# avroscope.net
KiCad netlist of a schematic drawn in Altium Designer
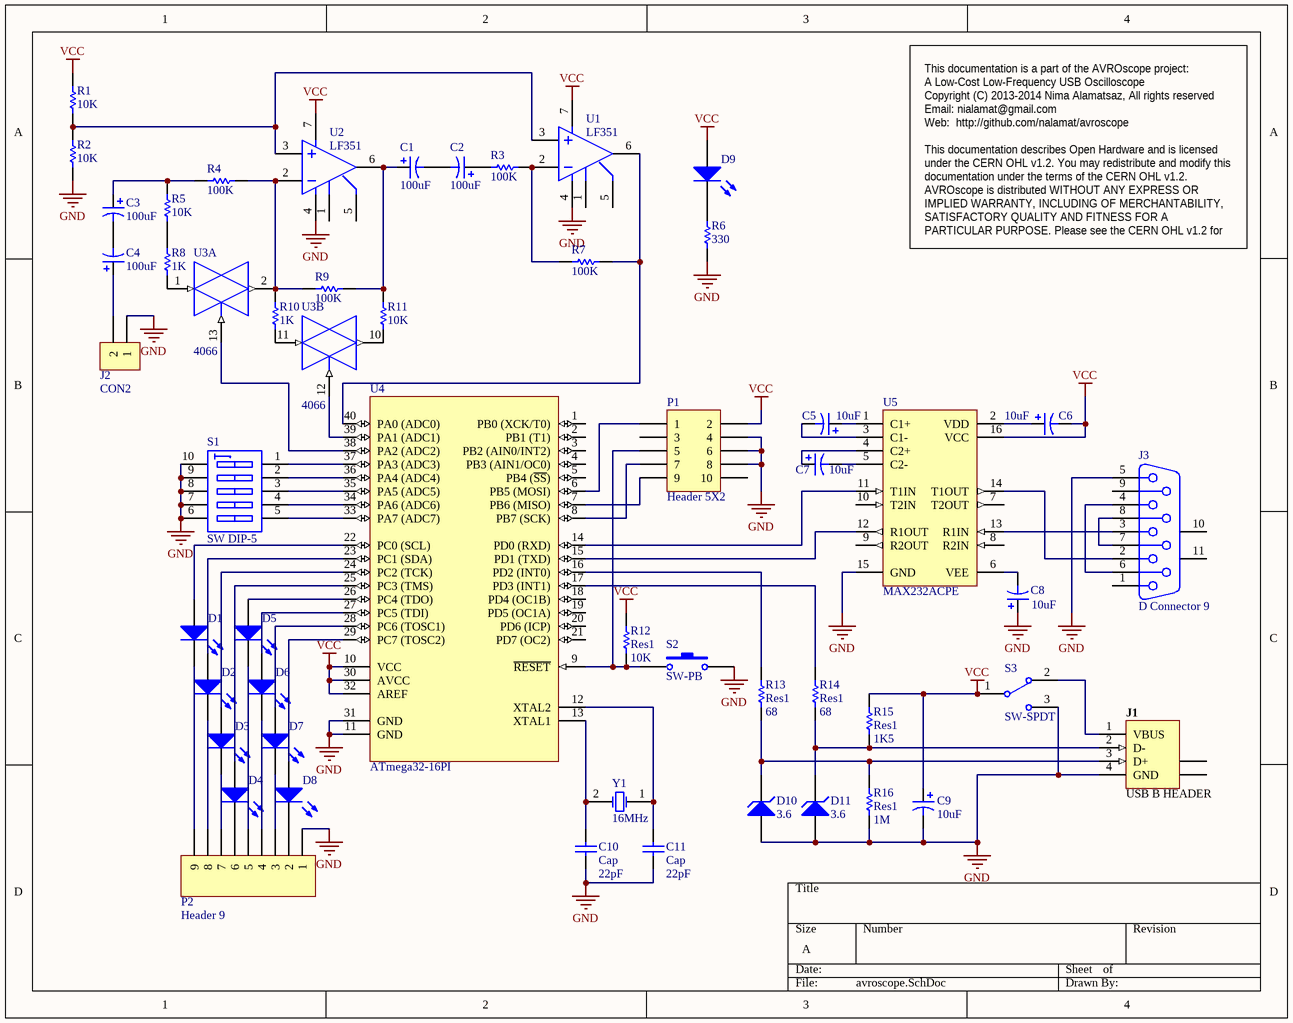
[diagram p0: avroscope.SchDoc]

(export (version "E")
  (design (tool "Eeschema 10.0.6"))
  (components
    (comp (ref "C1")
      (value "100uF")
      (footprint "RB.1/.2")
      (description "Polarized Capacitor (Radial)")
      (fields (field (name "Comment") "Cap Pol1") (field (name "PUBLISHER") "Altium Limited"))
      (libsource (lib "Miscellaneous Devices") (part "Cap Pol1"))
    )
    (comp (ref "C2")
      (value "100uF")
      (footprint "RB.1/.2")
      (description "Polarized Capacitor (Radial)")
      (fields (field (name "Comment") "Cap Pol1") (field (name "PUBLISHER") "Altium Limited"))
      (libsource (lib "Miscellaneous Devices") (part "Cap Pol1"))
    )
    (comp (ref "C3")
      (value "100uF")
      (footprint "RB.1/.2")
      (description "Polarized Capacitor (Radial)")
      (fields (field (name "Comment") "Cap Pol1") (field (name "PUBLISHER") "Altium Limited"))
      (libsource (lib "Miscellaneous Devices") (part "Cap Pol1"))
    )
    (comp (ref "C4")
      (value "100uF")
      (footprint "RB.1/.2")
      (description "Polarized Capacitor (Radial)")
      (fields (field (name "Comment") "Cap Pol1") (field (name "PUBLISHER") "Altium Limited"))
      (libsource (lib "Miscellaneous Devices") (part "Cap Pol1"))
    )
    (comp (ref "C5")
      (value "10uF")
      (footprint "RB.1/.2")
      (description "Polarized Capacitor (Radial)")
      (fields (field (name "Comment") "Cap Pol1") (field (name "PUBLISHER") "Altium Limited"))
      (libsource (lib "Miscellaneous Devices") (part "Cap Pol1"))
    )
    (comp (ref "C6")
      (value "10uF")
      (footprint "RB.1/.2")
      (description "Polarized Capacitor (Radial)")
      (fields (field (name "Comment") "Cap Pol1") (field (name "PUBLISHER") "Altium Limited"))
      (libsource (lib "Miscellaneous Devices") (part "Cap Pol1"))
    )
    (comp (ref "C7")
      (value "10uF")
      (footprint "RB.1/.2")
      (description "Polarized Capacitor (Radial)")
      (fields (field (name "Comment") "Cap Pol1") (field (name "PUBLISHER") "Altium Limited"))
      (libsource (lib "Miscellaneous Devices") (part "Cap Pol1"))
    )
    (comp (ref "C8")
      (value "10uF")
      (footprint "RB.1/.2")
      (description "Polarized Capacitor (Radial)")
      (fields (field (name "Comment") "Cap Pol1") (field (name "PUBLISHER") "Altium Limited"))
      (libsource (lib "Miscellaneous Devices") (part "Cap Pol1"))
    )
    (comp (ref "C9")
      (value "10uF")
      (footprint "RB.1/.2")
      (description "Polarized Capacitor (Radial)")
      (fields (field (name "Comment") "Cap Pol1") (field (name "PUBLISHER") "Altium Limited"))
      (libsource (lib "Miscellaneous Devices") (part "Cap Pol1"))
    )
    (comp (ref "C10")
      (value "Cap")
      (footprint "RAD0.1")
      (description "Capacitor")
      (fields (field (name "ALTIUM_VALUE") "22pF") (field (name "PUBLISHER") "Altium Limited"))
      (libsource (lib "Miscellaneous Devices") (part "Cap"))
    )
    (comp (ref "C11")
      (value "Cap")
      (footprint "RAD0.1")
      (description "Capacitor")
      (fields (field (name "ALTIUM_VALUE") "22pF") (field (name "PUBLISHER") "Altium Limited"))
      (libsource (lib "Miscellaneous Devices") (part "Cap"))
    )
    (comp (ref "D1")
      (value "LED1")
      (footprint "LED .1")
      (description "Typical RED GaAs LED")
      (fields (field (name "PUBLISHER") "Altium Limited"))
      (libsource (lib "Miscellaneous Devices") (part "LED1"))
    )
    (comp (ref "D2")
      (value "LED1")
      (footprint "LED .1")
      (description "Typical RED GaAs LED")
      (fields (field (name "PUBLISHER") "Altium Limited"))
      (libsource (lib "Miscellaneous Devices") (part "LED1"))
    )
    (comp (ref "D3")
      (value "LED1")
      (footprint "LED .1")
      (description "Typical RED GaAs LED")
      (fields (field (name "PUBLISHER") "Altium Limited"))
      (libsource (lib "Miscellaneous Devices") (part "LED1"))
    )
    (comp (ref "D4")
      (value "LED1")
      (footprint "LED .1")
      (description "Typical RED GaAs LED")
      (fields (field (name "PUBLISHER") "Altium Limited"))
      (libsource (lib "Miscellaneous Devices") (part "LED1"))
    )
    (comp (ref "D5")
      (value "LED1")
      (footprint "LED .1")
      (description "Typical RED GaAs LED")
      (fields (field (name "PUBLISHER") "Altium Limited"))
      (libsource (lib "Miscellaneous Devices") (part "LED1"))
    )
    (comp (ref "D6")
      (value "LED1")
      (footprint "LED .1")
      (description "Typical RED GaAs LED")
      (fields (field (name "PUBLISHER") "Altium Limited"))
      (libsource (lib "Miscellaneous Devices") (part "LED1"))
    )
    (comp (ref "D7")
      (value "LED1")
      (footprint "LED .1")
      (description "Typical RED GaAs LED")
      (fields (field (name "PUBLISHER") "Altium Limited"))
      (libsource (lib "Miscellaneous Devices") (part "LED1"))
    )
    (comp (ref "D8")
      (value "LED1")
      (footprint "LED .1")
      (description "Typical RED GaAs LED")
      (fields (field (name "PUBLISHER") "Altium Limited"))
      (libsource (lib "Miscellaneous Devices") (part "LED1"))
    )
    (comp (ref "D9")
      (value "LED1")
      (footprint "LED .1")
      (description "Typical RED GaAs LED")
      (fields (field (name "PUBLISHER") "Altium Limited"))
      (libsource (lib "Miscellaneous Devices") (part "LED1"))
    )
    (comp (ref "D10")
      (value "3.6")
      (footprint "Diode .3 .03")
      (description "Zener Diode")
      (fields (field (name "PUBLISHER") "Altium Limited"))
      (libsource (lib "Miscellaneous Devices") (part "D Zener"))
    )
    (comp (ref "D11")
      (value "3.6")
      (footprint "Diode .3 .03")
      (description "Zener Diode")
      (fields (field (name "PUBLISHER") "Altium Limited"))
      (libsource (lib "Miscellaneous Devices") (part "D Zener"))
    )
    (comp (ref "J1")
      (value "USB B HEADER")
      (footprint "neolib:USB-B")
      (description "Connector, USB B Type, Right Angle, Thru Hole, White")
      (libsource (lib "altium-import") (part "root_0_CON-USBB-6-RA_"))
    )
    (comp (ref "J2")
      (value "CON2")
      (footprint "neolib:Header2 .2 .055")
      (description "Connector")
      (libsource (lib "Miscellaneous Connectors") (part "CON2"))
    )
    (comp (ref "J3")
      (value "D Connector 9")
      (footprint "neolib:DB9")
      (description "Receptacle Assembly, 9 Position, Right Angle")
      (fields (field (name "PUBLISHER") "Altium Limited"))
      (libsource (lib "Miscellaneous Connectors") (part "D Connector 9"))
    )
    (comp (ref "P1")
      (value "Header 5X2")
      (footprint "ISP")
      (description "Header, 5-Pin, Dual row")
      (fields (field (name "PUBLISHER") "Altium Limited"))
      (libsource (lib "Miscellaneous Connectors") (part "Header 5X2"))
    )
    (comp (ref "P2")
      (value "Header 9")
      (footprint "SIL.1/9")
      (description "Header, 9-Pin")
      (fields (field (name "PUBLISHER") "Altium Limited"))
      (libsource (lib "Miscellaneous Connectors") (part "Header 9"))
    )
    (comp (ref "R1")
      (value "10K")
      (footprint "AXIAL0.4")
      (description "Resistor")
      (fields (field (name "Comment") "Res1") (field (name "PUBLISHER") "Altium Limited"))
      (libsource (lib "Miscellaneous Devices") (part "Res1"))
    )
    (comp (ref "R2")
      (value "10K")
      (footprint "AXIAL0.4")
      (description "Resistor")
      (fields (field (name "Comment") "Res1") (field (name "PUBLISHER") "Altium Limited"))
      (libsource (lib "Miscellaneous Devices") (part "Res1"))
    )
    (comp (ref "R3")
      (value "100K")
      (footprint "AXIAL0.4")
      (description "Resistor")
      (fields (field (name "Comment") "Res1") (field (name "PUBLISHER") "Altium Limited"))
      (libsource (lib "Miscellaneous Devices") (part "Res1"))
    )
    (comp (ref "R4")
      (value "100K")
      (footprint "AXIAL0.4")
      (description "Resistor")
      (fields (field (name "Comment") "Res1") (field (name "PUBLISHER") "Altium Limited"))
      (libsource (lib "Miscellaneous Devices") (part "Res1"))
    )
    (comp (ref "R5")
      (value "10K")
      (footprint "AXIAL0.4")
      (description "Resistor")
      (fields (field (name "Comment") "Res1") (field (name "PUBLISHER") "Altium Limited"))
      (libsource (lib "Miscellaneous Devices") (part "Res1"))
    )
    (comp (ref "R6")
      (value "330")
      (footprint "AXIAL0.4")
      (description "Resistor")
      (fields (field (name "Comment") "Res1") (field (name "PUBLISHER") "Altium Limited"))
      (libsource (lib "Miscellaneous Devices") (part "Res1"))
    )
    (comp (ref "R7")
      (value "100K")
      (footprint "AXIAL0.4")
      (description "Resistor")
      (fields (field (name "Comment") "Res1") (field (name "PUBLISHER") "Altium Limited"))
      (libsource (lib "Miscellaneous Devices") (part "Res1"))
    )
    (comp (ref "R8")
      (value "1K")
      (footprint "AXIAL0.4")
      (description "Resistor")
      (fields (field (name "Comment") "Res1") (field (name "PUBLISHER") "Altium Limited"))
      (libsource (lib "Miscellaneous Devices") (part "Res1"))
    )
    (comp (ref "R9")
      (value "100K")
      (footprint "AXIAL0.4")
      (description "Resistor")
      (fields (field (name "Comment") "Res1") (field (name "PUBLISHER") "Altium Limited"))
      (libsource (lib "Miscellaneous Devices") (part "Res1"))
    )
    (comp (ref "R10")
      (value "1K")
      (footprint "AXIAL0.4")
      (description "Resistor")
      (fields (field (name "Comment") "Res1") (field (name "PUBLISHER") "Altium Limited"))
      (libsource (lib "Miscellaneous Devices") (part "Res1"))
    )
    (comp (ref "R11")
      (value "10K")
      (footprint "AXIAL0.4")
      (description "Resistor")
      (fields (field (name "Comment") "Res1") (field (name "PUBLISHER") "Altium Limited"))
      (libsource (lib "Miscellaneous Devices") (part "Res1"))
    )
    (comp (ref "R12")
      (value "Res1")
      (footprint "AXIAL0.4")
      (description "Resistor")
      (fields (field (name "ALTIUM_VALUE") "10K") (field (name "PUBLISHER") "Altium Limited"))
      (libsource (lib "Miscellaneous Devices") (part "Res1"))
    )
    (comp (ref "R13")
      (value "Res1")
      (footprint "AXIAL0.4")
      (description "Resistor")
      (fields (field (name "ALTIUM_VALUE") "68") (field (name "PUBLISHER") "Altium Limited"))
      (libsource (lib "Miscellaneous Devices") (part "Res1"))
    )
    (comp (ref "R14")
      (value "Res1")
      (footprint "AXIAL0.4")
      (description "Resistor")
      (fields (field (name "ALTIUM_VALUE") "68") (field (name "PUBLISHER") "Altium Limited"))
      (libsource (lib "Miscellaneous Devices") (part "Res1"))
    )
    (comp (ref "R15")
      (value "Res1")
      (footprint "AXIAL0.4")
      (description "Resistor")
      (fields (field (name "ALTIUM_VALUE") "1K5") (field (name "PUBLISHER") "Altium Limited"))
      (libsource (lib "Miscellaneous Devices") (part "Res1"))
    )
    (comp (ref "R16")
      (value "Res1")
      (footprint "AXIAL0.4")
      (description "Resistor")
      (fields (field (name "ALTIUM_VALUE") "1M") (field (name "PUBLISHER") "Altium Limited"))
      (libsource (lib "Miscellaneous Devices") (part "Res1"))
    )
    (comp (ref "S1")
      (value "SW DIP-5")
      (footprint "DIP10e")
      (description "DIP Switch, 5 Position, SPST")
      (fields (field (name "PUBLISHER") "Altium Limited"))
      (libsource (lib "Miscellaneous Devices") (part "SW DIP-5"))
    )
    (comp (ref "S2")
      (value "SW-PB")
      (footprint "SIP2")
      (description "Switch")
      (fields (field (name "PUBLISHER") "Altium Limited"))
      (libsource (lib "Miscellaneous Devices") (part "SW-PB"))
    )
    (comp (ref "S3")
      (value "SW-SPDT")
      (footprint "SW DPDT")
      (description "SPDT Subminiature Toggle Switch, Right Angle Mounting, Vertical Actuation")
      (fields (field (name "PUBLISHER") "Altium Limited"))
      (libsource (lib "Miscellaneous Devices_1") (part "SW-SPDT"))
    )
    (comp (ref "U1")
      (value "LF351")
      (footprint "DIP8e")
      (libsource (lib "Protel DOS Schematic") (part "741"))
    )
    (comp (ref "U2")
      (value "LF351")
      (footprint "DIP8e")
      (libsource (lib "Protel DOS Schematic") (part "741"))
    )
    (comp (ref "U3")
      (value "4066")
      (footprint "DIP14e")
      (libsource (lib "Protel DOS Schematic") (part "4066"))
    )
    (comp (ref "U4")
      (value "ATmega32-16PI")
      (footprint "DIP40E-600")
      (description "8-Bit AVR Microcontroller with 32K Bytes of In-System Programmable Flash Memory")
      (fields (field (name "PUBLISHER") "Altium Limited"))
      (libsource (lib "Atmel Microcontroller 8-Bit AVR") (part "ATmega32-16PI"))
    )
    (comp (ref "U5")
      (value "MAX232ACPE")
      (footprint "DIP16e")
      (description "+5V Powered, Multi-Channel RS-232 Driver/Receiver")
      (fields (field (name "PUBLISHER") "Altium Limited"))
      (libsource (lib "Maxim Communication Transceiver") (part "MAX232ACPE"))
    )
    (comp (ref "Y1")
      (value "16MHz")
      (footprint "XTAL1")
      (description "Crystal Oscillator")
      (fields (field (name "PUBLISHER") "Altium Limited"))
      (libsource (lib "Miscellaneous Devices") (part "XTAL"))
    )
  )
  (nets
    (net (code "1") (name "GND") (class "Default")
      (node (ref "C10") (pin "1") (pinfunction "1_1") (pintype "passive"))
      (node (ref "C11") (pin "1") (pinfunction "1_1") (pintype "passive"))
      (node (ref "C8") (pin "1") (pinfunction "1_1") (pintype "passive"))
      (node (ref "C9") (pin "2") (pinfunction "2_2") (pintype "passive"))
      (node (ref "D10") (pin "1") (pinfunction "A_1") (pintype "passive"))
      (node (ref "D11") (pin "1") (pinfunction "A_1") (pintype "passive"))
      (node (ref "J1") (pin "4") (pinfunction "GND_4") (pintype "power_in"))
      (node (ref "J2") (pin "1") (pinfunction "1_1") (pintype "passive"))
      (node (ref "J3") (pin "5") (pinfunction "5_5") (pintype "passive"))
      (node (ref "P1") (pin "4") (pinfunction "4_4") (pintype "passive"))
      (node (ref "P1") (pin "6") (pinfunction "6_6") (pintype "passive"))
      (node (ref "P1") (pin "8") (pinfunction "8_8") (pintype "passive"))
      (node (ref "P2") (pin "1") (pinfunction "1_1") (pintype "passive"))
      (node (ref "R16") (pin "1") (pinfunction "1_1") (pintype "passive"))
      (node (ref "R2") (pin "1") (pinfunction "1_1") (pintype "passive"))
      (node (ref "R6") (pin "1") (pinfunction "1_1") (pintype "passive"))
      (node (ref "S1") (pin "10") (pinfunction "B1_10") (pintype "passive"))
      (node (ref "S1") (pin "6") (pinfunction "B5_6") (pintype "passive"))
      (node (ref "S1") (pin "7") (pinfunction "B4_7") (pintype "passive"))
      (node (ref "S1") (pin "8") (pinfunction "B3_8") (pintype "passive"))
      (node (ref "S1") (pin "9") (pinfunction "B2_9") (pintype "passive"))
      (node (ref "S2") (pin "2") (pinfunction "2_2") (pintype "passive"))
      (node (ref "S3") (pin "3") (pintype "passive"))
      (node (ref "U1") (pin "4") (pintype "passive"))
      (node (ref "U2") (pin "4") (pintype "passive"))
      (node (ref "U3") (pin "7") (pinfunction "GND_7") (pintype "power_in"))
      (node (ref "U4") (pin "11") (pinfunction "GND_11") (pintype "power_in"))
      (node (ref "U4") (pin "31") (pinfunction "GND_31") (pintype "power_in"))
      (node (ref "U5") (pin "15") (pinfunction "GND_15") (pintype "power_in"))
    )
    (net (code "2") (name "Net-(C1-Pad1)") (class "Default")
      (node (ref "C1") (pin "1") (pinfunction "1_1") (pintype "passive"))
      (node (ref "R11") (pin "2") (pinfunction "2_2") (pintype "passive"))
      (node (ref "R9") (pin "2") (pinfunction "2_2") (pintype "passive"))
      (node (ref "U2") (pin "6") (pintype "passive"))
    )
    (net (code "3") (name "Net-(C1-Pad2)") (class "Default")
      (node (ref "C1") (pin "2") (pinfunction "2_2") (pintype "passive"))
      (node (ref "C2") (pin "2") (pinfunction "2_2") (pintype "passive"))
    )
    (net (code "4") (name "Net-(C2-Pad1)") (class "Default")
      (node (ref "C2") (pin "1") (pinfunction "1_1") (pintype "passive"))
      (node (ref "R3") (pin "1") (pinfunction "1_1") (pintype "passive"))
    )
    (net (code "5") (name "Net-(C3-Pad1)") (class "Default")
      (node (ref "C3") (pin "1") (pinfunction "1_1") (pintype "passive"))
      (node (ref "R4") (pin "1") (pinfunction "1_1") (pintype "passive"))
      (node (ref "R5") (pin "2") (pinfunction "2_2") (pintype "passive"))
    )
    (net (code "6") (name "Net-(C3-Pad2)") (class "Default")
      (node (ref "C3") (pin "2") (pinfunction "2_2") (pintype "passive"))
      (node (ref "C4") (pin "2") (pinfunction "2_2") (pintype "passive"))
    )
    (net (code "7") (name "Net-(C4-Pad1)") (class "Default")
      (node (ref "C4") (pin "1") (pinfunction "1_1") (pintype "passive"))
      (node (ref "J2") (pin "2") (pinfunction "2_2") (pintype "passive"))
    )
    (net (code "8") (name "Net-(D1-A)") (class "Default")
      (node (ref "D1") (pin "1") (pinfunction "A_1") (pintype "passive"))
      (node (ref "U4") (pin "22") (pinfunction "PC0_(SCL)_22") (pintype "bidirectional"))
    )
    (net (code "9") (name "Net-(D1-K)") (class "Default")
      (node (ref "D1") (pin "2") (pinfunction "K_2") (pintype "passive"))
      (node (ref "P2") (pin "9") (pinfunction "9_9") (pintype "passive"))
    )
    (net (code "10") (name "Net-(D2-A)") (class "Default")
      (node (ref "D2") (pin "1") (pinfunction "A_1") (pintype "passive"))
      (node (ref "U4") (pin "23") (pinfunction "PC1_(SDA)_23") (pintype "bidirectional"))
    )
    (net (code "11") (name "Net-(D2-K)") (class "Default")
      (node (ref "D2") (pin "2") (pinfunction "K_2") (pintype "passive"))
      (node (ref "P2") (pin "8") (pinfunction "8_8") (pintype "passive"))
    )
    (net (code "12") (name "Net-(D3-A)") (class "Default")
      (node (ref "D3") (pin "1") (pinfunction "A_1") (pintype "passive"))
      (node (ref "U4") (pin "24") (pinfunction "PC2_(TCK)_24") (pintype "bidirectional"))
    )
    (net (code "13") (name "Net-(D3-K)") (class "Default")
      (node (ref "D3") (pin "2") (pinfunction "K_2") (pintype "passive"))
      (node (ref "P2") (pin "7") (pinfunction "7_7") (pintype "passive"))
    )
    (net (code "14") (name "Net-(D4-A)") (class "Default")
      (node (ref "D4") (pin "1") (pinfunction "A_1") (pintype "passive"))
      (node (ref "U4") (pin "25") (pinfunction "PC3_(TMS)_25") (pintype "bidirectional"))
    )
    (net (code "15") (name "Net-(D4-K)") (class "Default")
      (node (ref "D4") (pin "2") (pinfunction "K_2") (pintype "passive"))
      (node (ref "P2") (pin "6") (pinfunction "6_6") (pintype "passive"))
    )
    (net (code "16") (name "Net-(D5-A)") (class "Default")
      (node (ref "D5") (pin "1") (pinfunction "A_1") (pintype "passive"))
      (node (ref "U4") (pin "26") (pinfunction "PC4_(TDO)_26") (pintype "bidirectional"))
    )
    (net (code "17") (name "Net-(D5-K)") (class "Default")
      (node (ref "D5") (pin "2") (pinfunction "K_2") (pintype "passive"))
      (node (ref "P2") (pin "5") (pinfunction "5_5") (pintype "passive"))
    )
    (net (code "18") (name "Net-(D6-A)") (class "Default")
      (node (ref "D6") (pin "1") (pinfunction "A_1") (pintype "passive"))
      (node (ref "U4") (pin "27") (pinfunction "PC5_(TDI)_27") (pintype "bidirectional"))
    )
    (net (code "19") (name "Net-(D6-K)") (class "Default")
      (node (ref "D6") (pin "2") (pinfunction "K_2") (pintype "passive"))
      (node (ref "P2") (pin "4") (pinfunction "4_4") (pintype "passive"))
    )
    (net (code "20") (name "Net-(D7-A)") (class "Default")
      (node (ref "D7") (pin "1") (pinfunction "A_1") (pintype "passive"))
      (node (ref "U4") (pin "28") (pinfunction "PC6_(TOSC1)_28") (pintype "bidirectional"))
    )
    (net (code "21") (name "Net-(D7-K)") (class "Default")
      (node (ref "D7") (pin "2") (pinfunction "K_2") (pintype "passive"))
      (node (ref "P2") (pin "3") (pinfunction "3_3") (pintype "passive"))
    )
    (net (code "22") (name "Net-(D8-A)") (class "Default")
      (node (ref "D8") (pin "1") (pinfunction "A_1") (pintype "passive"))
      (node (ref "U4") (pin "29") (pinfunction "PC7_(TOSC2)_29") (pintype "bidirectional"))
    )
    (net (code "23") (name "Net-(D8-K)") (class "Default")
      (node (ref "D8") (pin "2") (pinfunction "K_2") (pintype "passive"))
      (node (ref "P2") (pin "2") (pinfunction "2_2") (pintype "passive"))
    )
    (net (code "24") (name "Net-(D9-K)") (class "Default")
      (node (ref "D9") (pin "2") (pinfunction "K_2") (pintype "passive"))
      (node (ref "R6") (pin "2") (pinfunction "2_2") (pintype "passive"))
    )
    (net (code "25") (name "Net-(D10-K)") (class "Default")
      (node (ref "D10") (pin "2") (pinfunction "K_2") (pintype "passive"))
      (node (ref "J1") (pin "3") (pinfunction "D+_3") (pintype "input"))
      (node (ref "R13") (pin "1") (pinfunction "1_1") (pintype "passive"))
      (node (ref "R16") (pin "2") (pinfunction "2_2") (pintype "passive"))
    )
    (net (code "26") (name "Net-(D11-K)") (class "Default")
      (node (ref "D11") (pin "2") (pinfunction "K_2") (pintype "passive"))
      (node (ref "J1") (pin "2") (pinfunction "D-_2") (pintype "input"))
      (node (ref "R14") (pin "1") (pinfunction "1_1") (pintype "passive"))
      (node (ref "R15") (pin "1") (pinfunction "1_1") (pintype "passive"))
    )
    (net (code "27") (name "Net-(J1-VBUS)") (class "Default")
      (node (ref "J1") (pin "1") (pinfunction "VBUS_1") (pintype "power_in"))
      (node (ref "S3") (pin "2") (pintype "passive"))
    )
    (net (code "28") (name "Net-(J3-Pad4)") (class "Default")
      (node (ref "J3") (pin "4") (pinfunction "4_4") (pintype "passive"))
      (node (ref "J3") (pin "6") (pinfunction "6_6") (pintype "passive"))
    )
    (net (code "29") (name "Net-(J3-Pad7)") (class "Default")
      (node (ref "J3") (pin "7") (pinfunction "7_7") (pintype "passive"))
      (node (ref "J3") (pin "8") (pinfunction "8_8") (pintype "passive"))
    )
    (net (code "30") (name "Net-(R1-Pad1)") (class "Default")
      (node (ref "R1") (pin "1") (pinfunction "1_1") (pintype "passive"))
      (node (ref "R2") (pin "2") (pinfunction "2_2") (pintype "passive"))
      (node (ref "U1") (pin "3") (pintype "passive"))
      (node (ref "U2") (pin "3") (pintype "passive"))
    )
    (net (code "31") (name "Net-(R3-Pad2)") (class "Default")
      (node (ref "R3") (pin "2") (pinfunction "2_2") (pintype "passive"))
      (node (ref "R7") (pin "1") (pinfunction "1_1") (pintype "passive"))
      (node (ref "U1") (pin "2") (pintype "passive"))
    )
    (net (code "32") (name "Net-(R5-Pad1)") (class "Default")
      (node (ref "R5") (pin "1") (pinfunction "1_1") (pintype "passive"))
      (node (ref "R8") (pin "2") (pinfunction "2_2") (pintype "passive"))
    )
    (net (code "33") (name "Net-(R8-Pad1)") (class "Default")
      (node (ref "R8") (pin "1") (pinfunction "1_1") (pintype "passive"))
      (node (ref "U3") (pin "1") (pintype "input"))
    )
    (net (code "34") (name "Net-(R10-Pad1)") (class "Default")
      (node (ref "R10") (pin "1") (pinfunction "1_1") (pintype "passive"))
      (node (ref "U3") (pin "11") (pintype "input"))
    )
    (net (code "35") (name "Net-(R10-Pad2)") (class "Default")
      (node (ref "R10") (pin "2") (pinfunction "2_2") (pintype "passive"))
      (node (ref "R4") (pin "2") (pinfunction "2_2") (pintype "passive"))
      (node (ref "R9") (pin "1") (pinfunction "1_1") (pintype "passive"))
      (node (ref "U2") (pin "2") (pintype "passive"))
      (node (ref "U3") (pin "2") (pintype "output"))
    )
    (net (code "36") (name "Net-(R11-Pad1)") (class "Default")
      (node (ref "R11") (pin "1") (pinfunction "1_1") (pintype "passive"))
      (node (ref "U3") (pin "10") (pintype "output"))
    )
    (net (code "37") (name "Net-(S1-A1)") (class "Default")
      (node (ref "S1") (pin "1") (pinfunction "A1_1") (pintype "passive"))
      (node (ref "U4") (pin "37") (pinfunction "PA3_(ADC3)_37") (pintype "bidirectional"))
    )
    (net (code "38") (name "Net-(S1-A2)") (class "Default")
      (node (ref "S1") (pin "2") (pinfunction "A2_2") (pintype "passive"))
      (node (ref "U4") (pin "36") (pinfunction "PA4_(ADC4)_36") (pintype "bidirectional"))
    )
    (net (code "39") (name "Net-(S1-A3)") (class "Default")
      (node (ref "S1") (pin "3") (pinfunction "A3_3") (pintype "passive"))
      (node (ref "U4") (pin "35") (pinfunction "PA5_(ADC5)_35") (pintype "bidirectional"))
    )
    (net (code "40") (name "Net-(S1-A4)") (class "Default")
      (node (ref "S1") (pin "4") (pinfunction "A4_4") (pintype "passive"))
      (node (ref "U4") (pin "34") (pinfunction "PA6_(ADC6)_34") (pintype "bidirectional"))
    )
    (net (code "41") (name "Net-(S1-A5)") (class "Default")
      (node (ref "S1") (pin "5") (pinfunction "A5_5") (pintype "passive"))
      (node (ref "U4") (pin "33") (pinfunction "PA7_(ADC7)_33") (pintype "bidirectional"))
    )
    (net (code "42") (name "Net-(U4-PA0_(ADC0))") (class "Default")
      (node (ref "R7") (pin "2") (pinfunction "2_2") (pintype "passive"))
      (node (ref "U1") (pin "6") (pintype "passive"))
      (node (ref "U4") (pin "40") (pinfunction "PA0_(ADC0)_40") (pintype "bidirectional"))
    )
    (net (code "43") (name "Net-(U4-PA1_(ADC1))") (class "Default")
      (node (ref "U3") (pin "12") (pintype "input"))
      (node (ref "U4") (pin "39") (pinfunction "PA1_(ADC1)_39") (pintype "bidirectional"))
    )
    (net (code "44") (name "Net-(U4-PA2_(ADC2))") (class "Default")
      (node (ref "U3") (pin "13") (pintype "input"))
      (node (ref "U4") (pin "38") (pinfunction "PA2_(ADC2)_38") (pintype "bidirectional"))
    )
    (net (code "45") (name "Net-(U4-PB5_(MOSI))") (class "Default")
      (node (ref "P1") (pin "1") (pinfunction "1_1") (pintype "passive"))
      (node (ref "U4") (pin "6") (pinfunction "PB5_(MOSI)_6") (pintype "bidirectional"))
    )
    (net (code "46") (name "Net-(U4-PB6_(MISO))") (class "Default")
      (node (ref "P1") (pin "9") (pinfunction "9_9") (pintype "passive"))
      (node (ref "U4") (pin "7") (pinfunction "PB6_(MISO)_7") (pintype "bidirectional"))
    )
    (net (code "47") (name "Net-(U4-PB7_(SCK))") (class "Default")
      (node (ref "P1") (pin "7") (pinfunction "7_7") (pintype "passive"))
      (node (ref "U4") (pin "8") (pinfunction "PB7_(SCK)_8") (pintype "bidirectional"))
    )
    (net (code "48") (name "Net-(U4-PD0_(RXD))") (class "Default")
      (node (ref "U4") (pin "14") (pinfunction "PD0_(RXD)_14") (pintype "bidirectional"))
      (node (ref "U5") (pin "11") (pinfunction "T1IN_11") (pintype "input"))
    )
    (net (code "49") (name "Net-(U4-PD1_(TXD))") (class "Default")
      (node (ref "U4") (pin "15") (pinfunction "PD1_(TXD)_15") (pintype "bidirectional"))
      (node (ref "U5") (pin "12") (pinfunction "R1OUT_12") (pintype "output"))
    )
    (net (code "50") (name "Net-(U4-PD2_(INT0))") (class "Default")
      (node (ref "R13") (pin "2") (pinfunction "2_2") (pintype "passive"))
      (node (ref "U4") (pin "16") (pinfunction "PD2_(INT0)_16") (pintype "bidirectional"))
    )
    (net (code "51") (name "Net-(U4-PD3_(INT1))") (class "Default")
      (node (ref "R14") (pin "2") (pinfunction "2_2") (pintype "passive"))
      (node (ref "U4") (pin "17") (pinfunction "PD3_(INT1)_17") (pintype "bidirectional"))
    )
    (net (code "52") (name "Net-(U4-XTAL1)") (class "Default")
      (node (ref "C10") (pin "2") (pinfunction "2_2") (pintype "passive"))
      (node (ref "U4") (pin "13") (pinfunction "XTAL1_13") (pintype "passive"))
      (node (ref "Y1") (pin "2") (pinfunction "OSC2_2") (pintype "passive"))
    )
    (net (code "53") (name "Net-(U4-XTAL2)") (class "Default")
      (node (ref "C11") (pin "2") (pinfunction "2_2") (pintype "passive"))
      (node (ref "U4") (pin "12") (pinfunction "XTAL2_12") (pintype "passive"))
      (node (ref "Y1") (pin "1") (pinfunction "OSC1_1") (pintype "passive"))
    )
    (net (code "54") (name "Net-(U4-~{RESET})") (class "Default")
      (node (ref "P1") (pin "5") (pinfunction "5_5") (pintype "passive"))
      (node (ref "R12") (pin "2") (pinfunction "2_2") (pintype "passive"))
      (node (ref "S2") (pin "1") (pinfunction "1_1") (pintype "passive"))
      (node (ref "U4") (pin "9") (pinfunction "~{RESET}_9") (pintype "input"))
    )
    (net (code "55") (name "Net-(U5-C1+)") (class "Default")
      (node (ref "C5") (pin "1") (pinfunction "1_1") (pintype "passive"))
      (node (ref "U5") (pin "1") (pinfunction "C1+_1") (pintype "passive"))
    )
    (net (code "56") (name "Net-(U5-C1-)") (class "Default")
      (node (ref "C5") (pin "2") (pinfunction "2_2") (pintype "passive"))
      (node (ref "U5") (pin "3") (pinfunction "C1-_3") (pintype "passive"))
    )
    (net (code "57") (name "Net-(U5-C2+)") (class "Default")
      (node (ref "C7") (pin "1") (pinfunction "1_1") (pintype "passive"))
      (node (ref "U5") (pin "4") (pinfunction "C2+_4") (pintype "passive"))
    )
    (net (code "58") (name "Net-(U5-C2-)") (class "Default")
      (node (ref "C7") (pin "2") (pinfunction "2_2") (pintype "passive"))
      (node (ref "U5") (pin "5") (pinfunction "C2-_5") (pintype "passive"))
    )
    (net (code "59") (name "Net-(U5-R1IN)") (class "Default")
      (node (ref "J3") (pin "3") (pinfunction "3_3") (pintype "passive"))
      (node (ref "U5") (pin "13") (pinfunction "R1IN_13") (pintype "input"))
    )
    (net (code "60") (name "Net-(U5-T1OUT)") (class "Default")
      (node (ref "J3") (pin "2") (pinfunction "2_2") (pintype "passive"))
      (node (ref "U5") (pin "14") (pinfunction "T1OUT_14") (pintype "output"))
    )
    (net (code "61") (name "Net-(U5-VDD)") (class "Default")
      (node (ref "C6") (pin "1") (pinfunction "1_1") (pintype "passive"))
      (node (ref "U5") (pin "2") (pinfunction "VDD_2") (pintype "power_in"))
    )
    (net (code "62") (name "Net-(U5-VEE)") (class "Default")
      (node (ref "C8") (pin "2") (pinfunction "2_2") (pintype "passive"))
      (node (ref "U5") (pin "6") (pinfunction "VEE_6") (pintype "power_in"))
    )
    (net (code "63") (name "VCC") (class "Default")
      (node (ref "C6") (pin "2") (pinfunction "2_2") (pintype "passive"))
      (node (ref "C9") (pin "1") (pinfunction "1_1") (pintype "passive"))
      (node (ref "D9") (pin "1") (pinfunction "A_1") (pintype "passive"))
      (node (ref "P1") (pin "2") (pinfunction "2_2") (pintype "passive"))
      (node (ref "R1") (pin "2") (pinfunction "2_2") (pintype "passive"))
      (node (ref "R12") (pin "1") (pinfunction "1_1") (pintype "passive"))
      (node (ref "R15") (pin "2") (pinfunction "2_2") (pintype "passive"))
      (node (ref "S3") (pin "1") (pintype "passive"))
      (node (ref "U1") (pin "7") (pintype "passive"))
      (node (ref "U2") (pin "7") (pintype "passive"))
      (node (ref "U3") (pin "14") (pinfunction "VCC_14") (pintype "power_in"))
      (node (ref "U4") (pin "10") (pinfunction "VCC_10") (pintype "power_in"))
      (node (ref "U4") (pin "30") (pinfunction "AVCC_30") (pintype "power_in"))
      (node (ref "U4") (pin "32") (pinfunction "AREF_32") (pintype "passive"))
      (node (ref "U5") (pin "16") (pinfunction "VCC_16") (pintype "power_in"))
    )
    (net (code "64") (name "unconnected-(J1-SHLD-Pad5)") (class "Default")
      (node (ref "J1") (pin "5") (pinfunction "SHLD_5") (pintype "passive"))
    )
    (net (code "65") (name "unconnected-(J1-SHLD-Pad6)") (class "Default")
      (node (ref "J1") (pin "6") (pinfunction "SHLD_6") (pintype "passive"))
    )
    (net (code "66") (name "unconnected-(J3-MH1-Pad10)") (class "Default")
      (node (ref "J3") (pin "10") (pinfunction "MH1_10") (pintype "passive"))
    )
    (net (code "67") (name "unconnected-(J3-MH2-Pad11)") (class "Default")
      (node (ref "J3") (pin "11") (pinfunction "MH2_11") (pintype "passive"))
    )
    (net (code "68") (name "unconnected-(J3-Pad1)") (class "Default")
      (node (ref "J3") (pin "1") (pinfunction "1_1") (pintype "passive"))
    )
    (net (code "69") (name "unconnected-(J3-Pad9)") (class "Default")
      (node (ref "J3") (pin "9") (pinfunction "9_9") (pintype "passive"))
    )
    (net (code "70") (name "unconnected-(P1-Pad3)") (class "Default")
      (node (ref "P1") (pin "3") (pinfunction "3_3") (pintype "passive"))
    )
    (net (code "71") (name "unconnected-(P1-Pad10)") (class "Default")
      (node (ref "P1") (pin "10") (pinfunction "10_10") (pintype "passive"))
    )
    (net (code "72") (name "unconnected-(U1-Pad1)") (class "Default")
      (node (ref "U1") (pin "1") (pintype "passive"))
    )
    (net (code "73") (name "unconnected-(U1-Pad5)") (class "Default")
      (node (ref "U1") (pin "5") (pintype "passive"))
    )
    (net (code "74") (name "unconnected-(U2-Pad1)") (class "Default")
      (node (ref "U2") (pin "1") (pintype "passive"))
    )
    (net (code "75") (name "unconnected-(U2-Pad5)") (class "Default")
      (node (ref "U2") (pin "5") (pintype "passive"))
    )
    (net (code "76") (name "unconnected-(U4-PB0_(XCK{slash}T0)-Pad1)") (class "Default")
      (node (ref "U4") (pin "1") (pinfunction "PB0_(XCK/T0)_1") (pintype "bidirectional"))
    )
    (net (code "77") (name "unconnected-(U4-PB1_(T1)-Pad2)") (class "Default")
      (node (ref "U4") (pin "2") (pinfunction "PB1_(T1)_2") (pintype "bidirectional"))
    )
    (net (code "78") (name "unconnected-(U4-PB2_(AIN0{slash}INT2)-Pad3)") (class "Default")
      (node (ref "U4") (pin "3") (pinfunction "PB2_(AIN0/INT2)_3") (pintype "bidirectional"))
    )
    (net (code "79") (name "unconnected-(U4-PB3_(AIN1{slash}OC0)-Pad4)") (class "Default")
      (node (ref "U4") (pin "4") (pinfunction "PB3_(AIN1/OC0)_4") (pintype "bidirectional"))
    )
    (net (code "80") (name "unconnected-(U4-PB4_(~{SS})-Pad5)") (class "Default")
      (node (ref "U4") (pin "5") (pinfunction "PB4_(~{SS})_5") (pintype "bidirectional"))
    )
    (net (code "81") (name "unconnected-(U4-PD4_(OC1B)-Pad18)") (class "Default")
      (node (ref "U4") (pin "18") (pinfunction "PD4_(OC1B)_18") (pintype "bidirectional"))
    )
    (net (code "82") (name "unconnected-(U4-PD5_(OC1A)-Pad19)") (class "Default")
      (node (ref "U4") (pin "19") (pinfunction "PD5_(OC1A)_19") (pintype "bidirectional"))
    )
    (net (code "83") (name "unconnected-(U4-PD6_(ICP)-Pad20)") (class "Default")
      (node (ref "U4") (pin "20") (pinfunction "PD6_(ICP)_20") (pintype "bidirectional"))
    )
    (net (code "84") (name "unconnected-(U4-PD7_(OC2)-Pad21)") (class "Default")
      (node (ref "U4") (pin "21") (pinfunction "PD7_(OC2)_21") (pintype "bidirectional"))
    )
    (net (code "85") (name "unconnected-(U5-R2IN-Pad8)") (class "Default")
      (node (ref "U5") (pin "8") (pinfunction "R2IN_8") (pintype "input"))
    )
    (net (code "86") (name "unconnected-(U5-R2OUT-Pad9)") (class "Default")
      (node (ref "U5") (pin "9") (pinfunction "R2OUT_9") (pintype "output"))
    )
    (net (code "87") (name "unconnected-(U5-T2IN-Pad10)") (class "Default")
      (node (ref "U5") (pin "10") (pinfunction "T2IN_10") (pintype "input"))
    )
    (net (code "88") (name "unconnected-(U5-T2OUT-Pad7)") (class "Default")
      (node (ref "U5") (pin "7") (pinfunction "T2OUT_7") (pintype "output"))
    )
  )
)
